# G1Tech-LTC1966.net
KiCad netlist of a schematic drawn in EAGLE
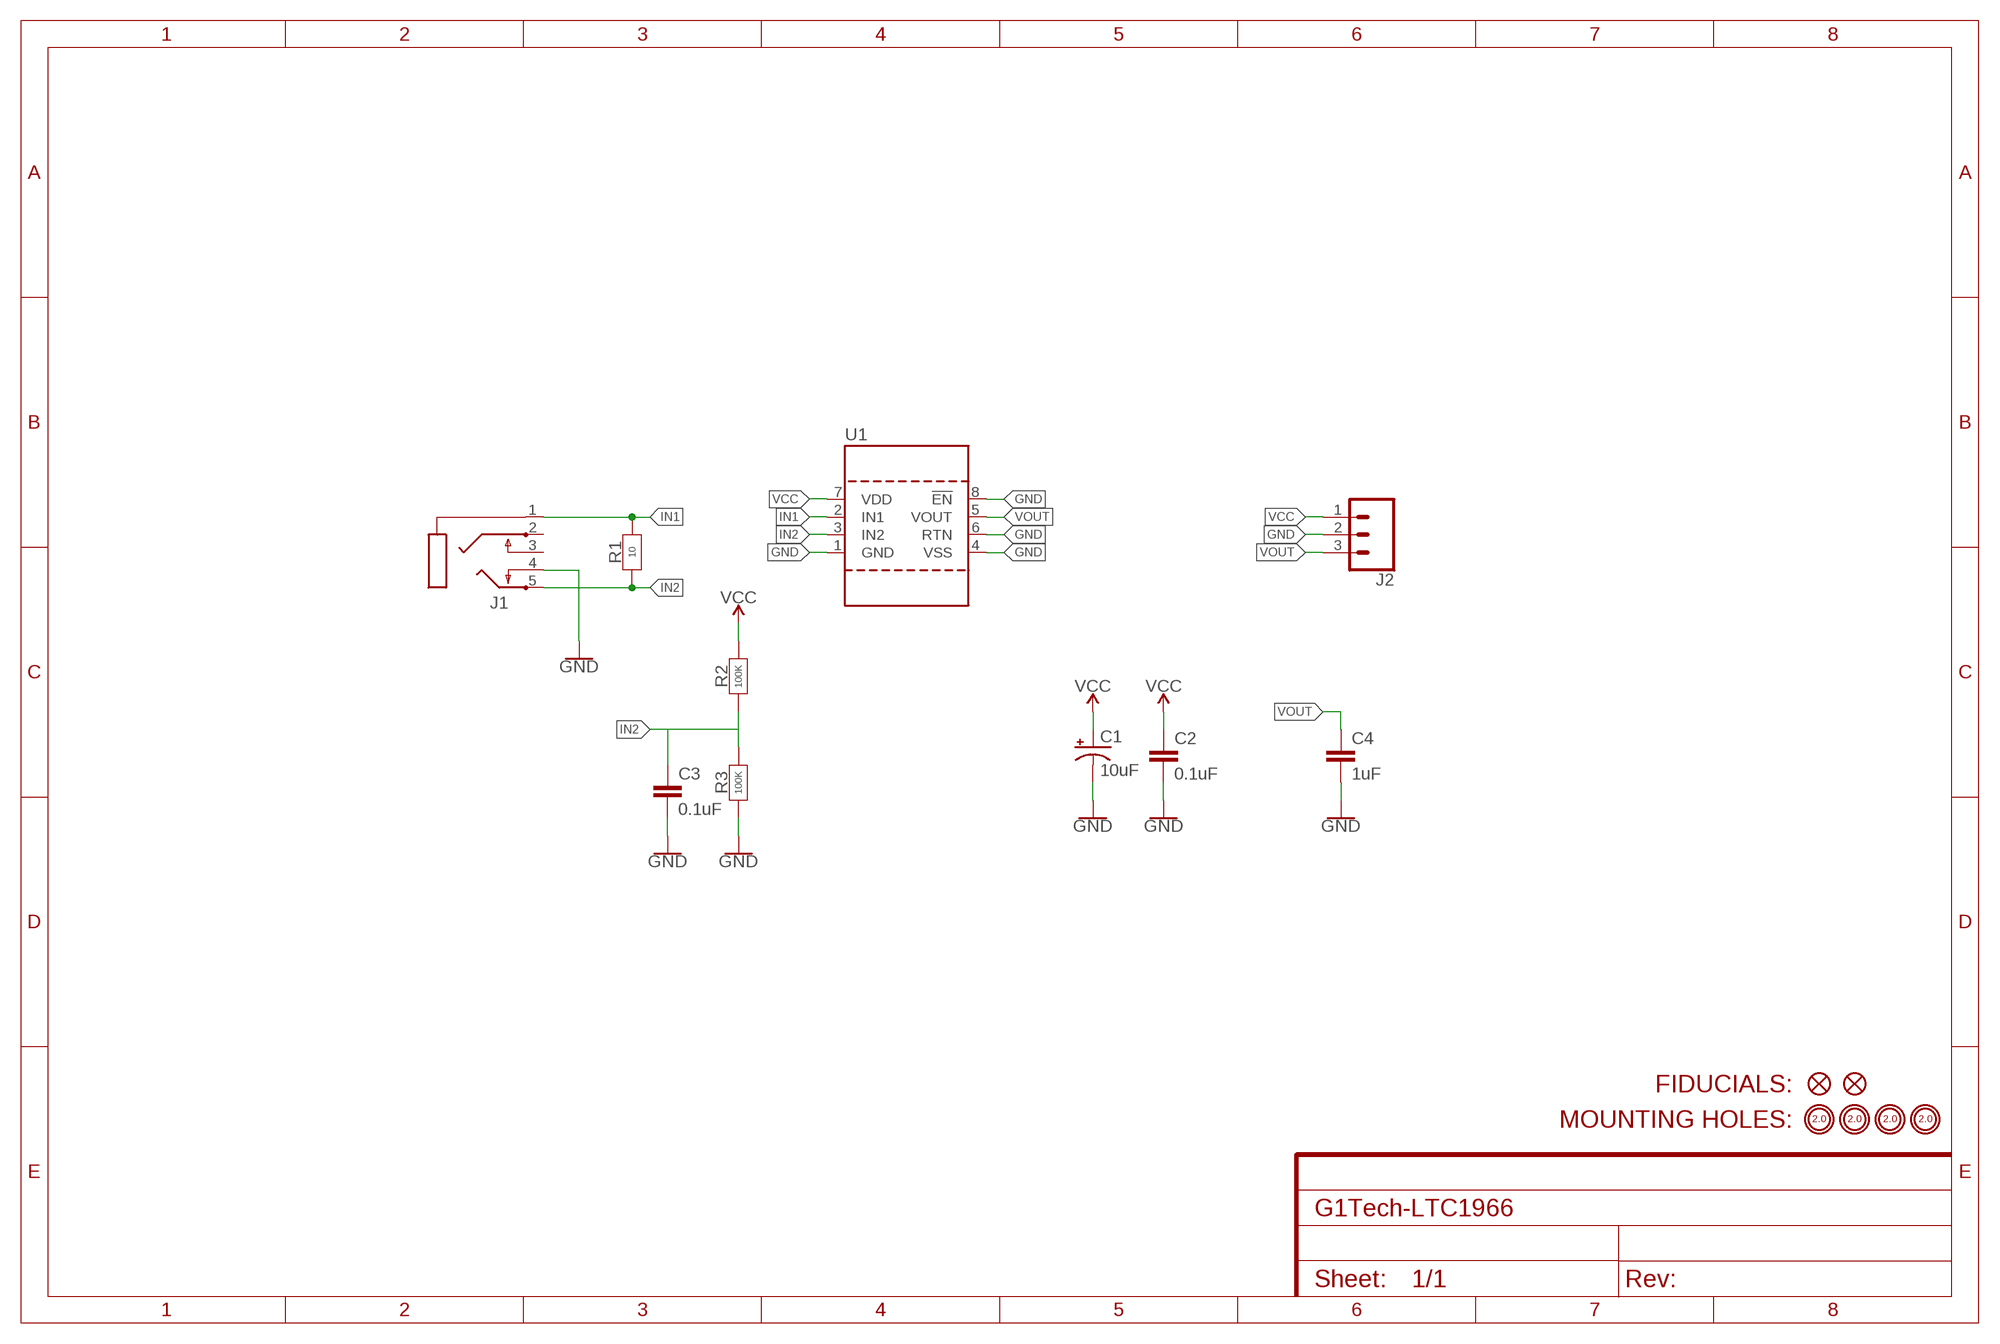
[diagram p0: schematic, sheet 1]

(export (version "E")
  (design (tool "Eeschema 10.0.6"))
  (components
    (comp (ref "C1")
      (value "10uF")
      (footprint "eagle-import:TYPE-A")
      (libsource (lib "eagle-import") (part "C-TYPE-A"))
    )
    (comp (ref "C2")
      (value "0.1uF")
      (footprint "eagle-import:C0603")
      (libsource (lib "eagle-import") (part "C0603"))
    )
    (comp (ref "C3")
      (value "0.1uF")
      (footprint "eagle-import:C0603")
      (libsource (lib "eagle-import") (part "C0603"))
    )
    (comp (ref "C4")
      (value "1uF")
      (footprint "eagle-import:C0603")
      (libsource (lib "eagle-import") (part "C0603"))
    )
    (comp (ref "FD1")
      (value "FIDUCIAL-1X2")
      (footprint "eagle-import:FIDUCIAL-1X2")
      (libsource (lib "eagle-import") (part "FIDUCIAL-1X2"))
    )
    (comp (ref "FD2")
      (value "FIDUCIAL-1X2")
      (footprint "eagle-import:FIDUCIAL-1X2")
      (libsource (lib "eagle-import") (part "FIDUCIAL-1X2"))
    )
    (comp (ref "H1")
      (value "MOUNTINGHOLE-PLATED-2.0")
      (footprint "eagle-import:MOUNTINGHOLE-PLATED-2.0")
      (libsource (lib "eagle-import") (part "MOUNTINGHOLE-PLATED-2.0"))
    )
    (comp (ref "H2")
      (value "MOUNTINGHOLE-PLATED-2.0")
      (footprint "eagle-import:MOUNTINGHOLE-PLATED-2.0")
      (libsource (lib "eagle-import") (part "MOUNTINGHOLE-PLATED-2.0"))
    )
    (comp (ref "H3")
      (value "MOUNTINGHOLE-PLATED-2.0")
      (footprint "eagle-import:MOUNTINGHOLE-PLATED-2.0")
      (libsource (lib "eagle-import") (part "MOUNTINGHOLE-PLATED-2.0"))
    )
    (comp (ref "H4")
      (value "MOUNTINGHOLE-PLATED-2.0")
      (footprint "eagle-import:MOUNTINGHOLE-PLATED-2.0")
      (libsource (lib "eagle-import") (part "MOUNTINGHOLE-PLATED-2.0"))
    )
    (comp (ref "J1")
      (value "PJ-3126-5A")
      (footprint "eagle-import:PJ-3126-5A")
      (libsource (lib "eagle-import") (part "PJ-3126-5A"))
    )
    (comp (ref "J2")
      (value "CONN-1X3")
      (footprint "eagle-import:1X03_NO_SILK")
      (libsource (lib "eagle-import") (part "CONN-1X3"))
    )
    (comp (ref "R1")
      (value "10")
      (footprint "eagle-import:YAGEO-R0603")
      (libsource (lib "eagle-import") (part "YAGEO-R0603"))
    )
    (comp (ref "R2")
      (value "100K")
      (footprint "eagle-import:YAGEO-R0603")
      (libsource (lib "eagle-import") (part "YAGEO-R0603"))
    )
    (comp (ref "R3")
      (value "100K")
      (footprint "eagle-import:YAGEO-R0603")
      (libsource (lib "eagle-import") (part "YAGEO-R0603"))
    )
    (comp (ref "U1")
      (value "LTC1966")
      (footprint "eagle-import:MS8")
      (libsource (lib "eagle-import") (part "LTC1966"))
    )
  )
  (nets
    (net (code "1") (name "GND") (class "Default")
      (node (ref "C1") (pin "C") (pinfunction "C_C") (pintype "passive"))
      (node (ref "C2") (pin "2") (pinfunction "2_2") (pintype "passive"))
      (node (ref "C3") (pin "2") (pinfunction "2_2") (pintype "passive"))
      (node (ref "C4") (pin "2") (pinfunction "2_2") (pintype "passive"))
      (node (ref "J1") (pin "4") (pinfunction "4_4") (pintype "passive"))
      (node (ref "J2") (pin "2") (pinfunction "2_2") (pintype "passive"))
      (node (ref "R3") (pin "1") (pinfunction "1_1") (pintype "passive"))
      (node (ref "U1") (pin "1") (pinfunction "GND_1") (pintype "power_in"))
      (node (ref "U1") (pin "4") (pinfunction "VSS_4") (pintype "power_in"))
      (node (ref "U1") (pin "6") (pinfunction "RTN_6") (pintype "output"))
      (node (ref "U1") (pin "8") (pinfunction "~{EN}_8") (pintype "bidirectional"))
    )
    (net (code "2") (name "IN1") (class "Default")
      (node (ref "J1") (pin "1") (pinfunction "1_1") (pintype "passive"))
      (node (ref "R1") (pin "2") (pinfunction "2_2") (pintype "passive"))
      (node (ref "U1") (pin "2") (pinfunction "IN1_2") (pintype "input"))
    )
    (net (code "3") (name "IN2") (class "Default")
      (node (ref "C3") (pin "1") (pinfunction "1_1") (pintype "passive"))
      (node (ref "J1") (pin "5") (pinfunction "5_5") (pintype "passive"))
      (node (ref "R1") (pin "1") (pinfunction "1_1") (pintype "passive"))
      (node (ref "R2") (pin "1") (pinfunction "1_1") (pintype "passive"))
      (node (ref "R3") (pin "2") (pinfunction "2_2") (pintype "passive"))
      (node (ref "U1") (pin "3") (pinfunction "IN2_3") (pintype "input"))
    )
    (net (code "4") (name "VCC") (class "Default")
      (node (ref "C1") (pin "A") (pinfunction "A_A") (pintype "passive"))
      (node (ref "C2") (pin "1") (pinfunction "1_1") (pintype "passive"))
      (node (ref "J2") (pin "1") (pinfunction "1_1") (pintype "passive"))
      (node (ref "R2") (pin "2") (pinfunction "2_2") (pintype "passive"))
      (node (ref "U1") (pin "7") (pinfunction "VDD_7") (pintype "power_in"))
    )
    (net (code "5") (name "VOUT") (class "Default")
      (node (ref "C4") (pin "1") (pinfunction "1_1") (pintype "passive"))
      (node (ref "J2") (pin "3") (pinfunction "3_3") (pintype "passive"))
      (node (ref "U1") (pin "5") (pinfunction "VOUT_5") (pintype "output"))
    )
    (net (code "6") (name "unconnected-(J1-Pad2)") (class "Default")
      (node (ref "J1") (pin "2") (pinfunction "2_2") (pintype "passive"))
    )
    (net (code "7") (name "unconnected-(J1-Pad3)") (class "Default")
      (node (ref "J1") (pin "3") (pinfunction "3_3") (pintype "passive"))
    )
  )
)
